# MiniWitch-Hardware.net
KiCad netlist of a schematic drawn in EasyEDA Pro
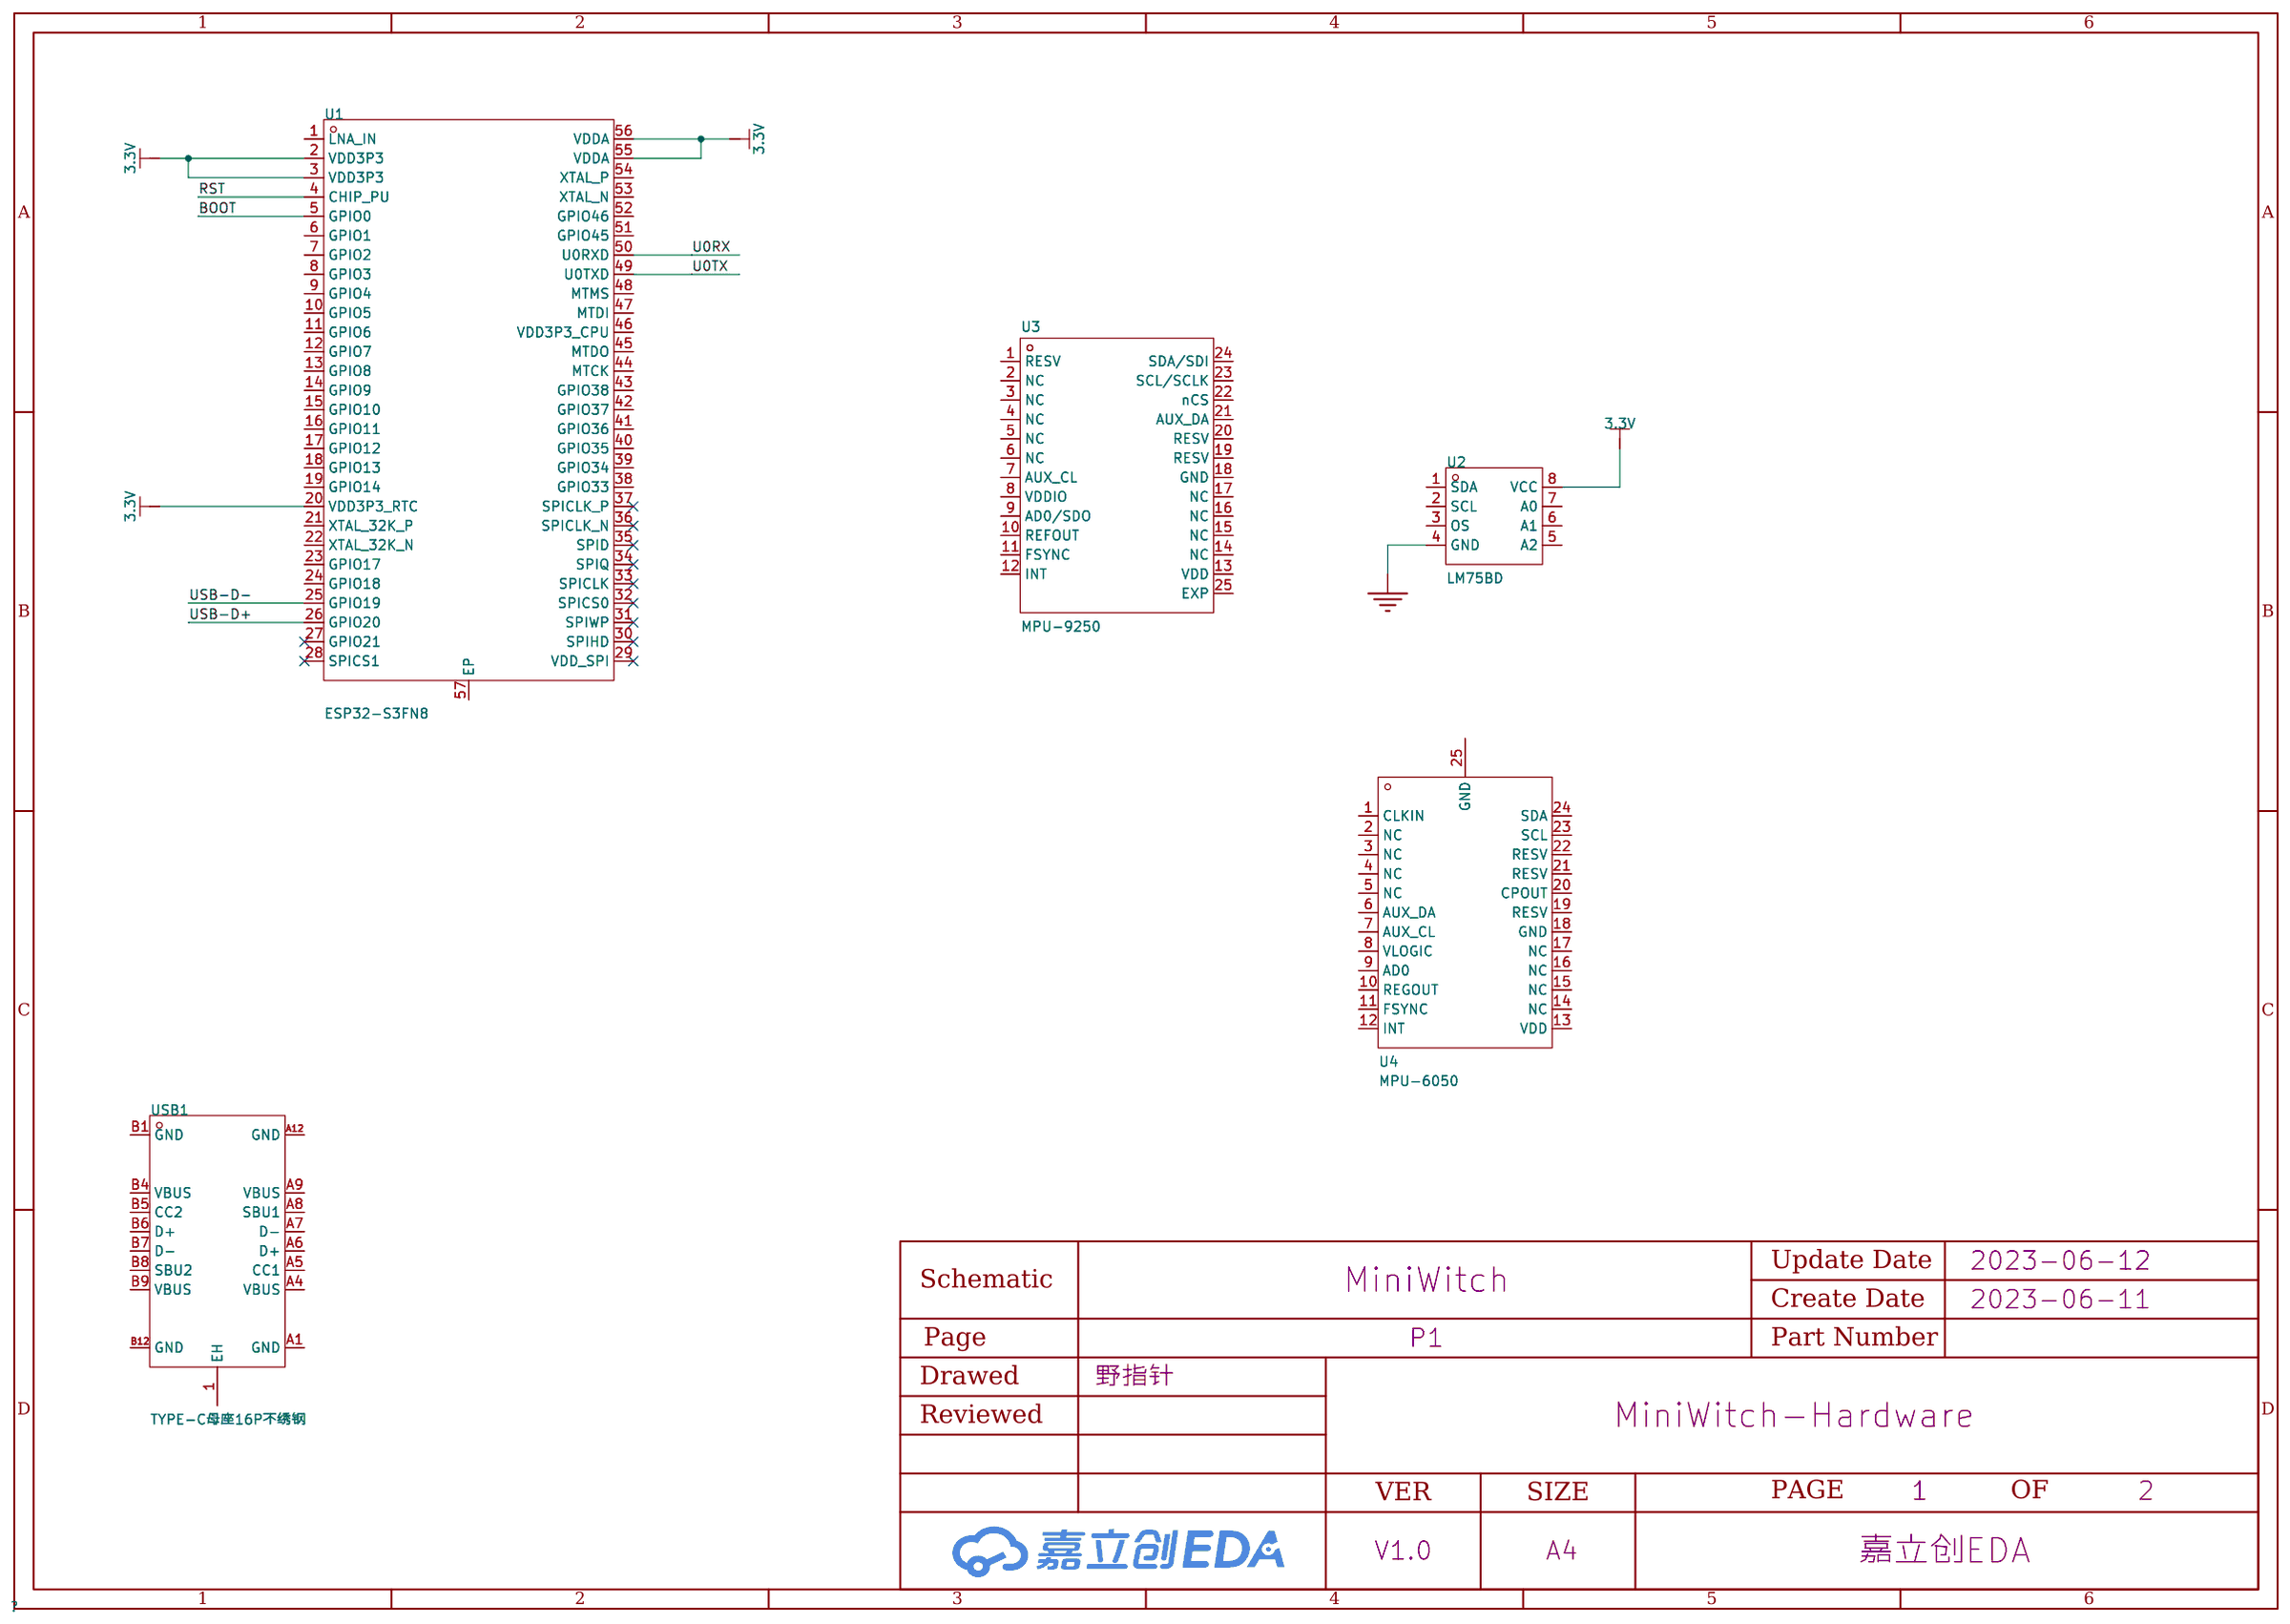
[diagram p0: P1]
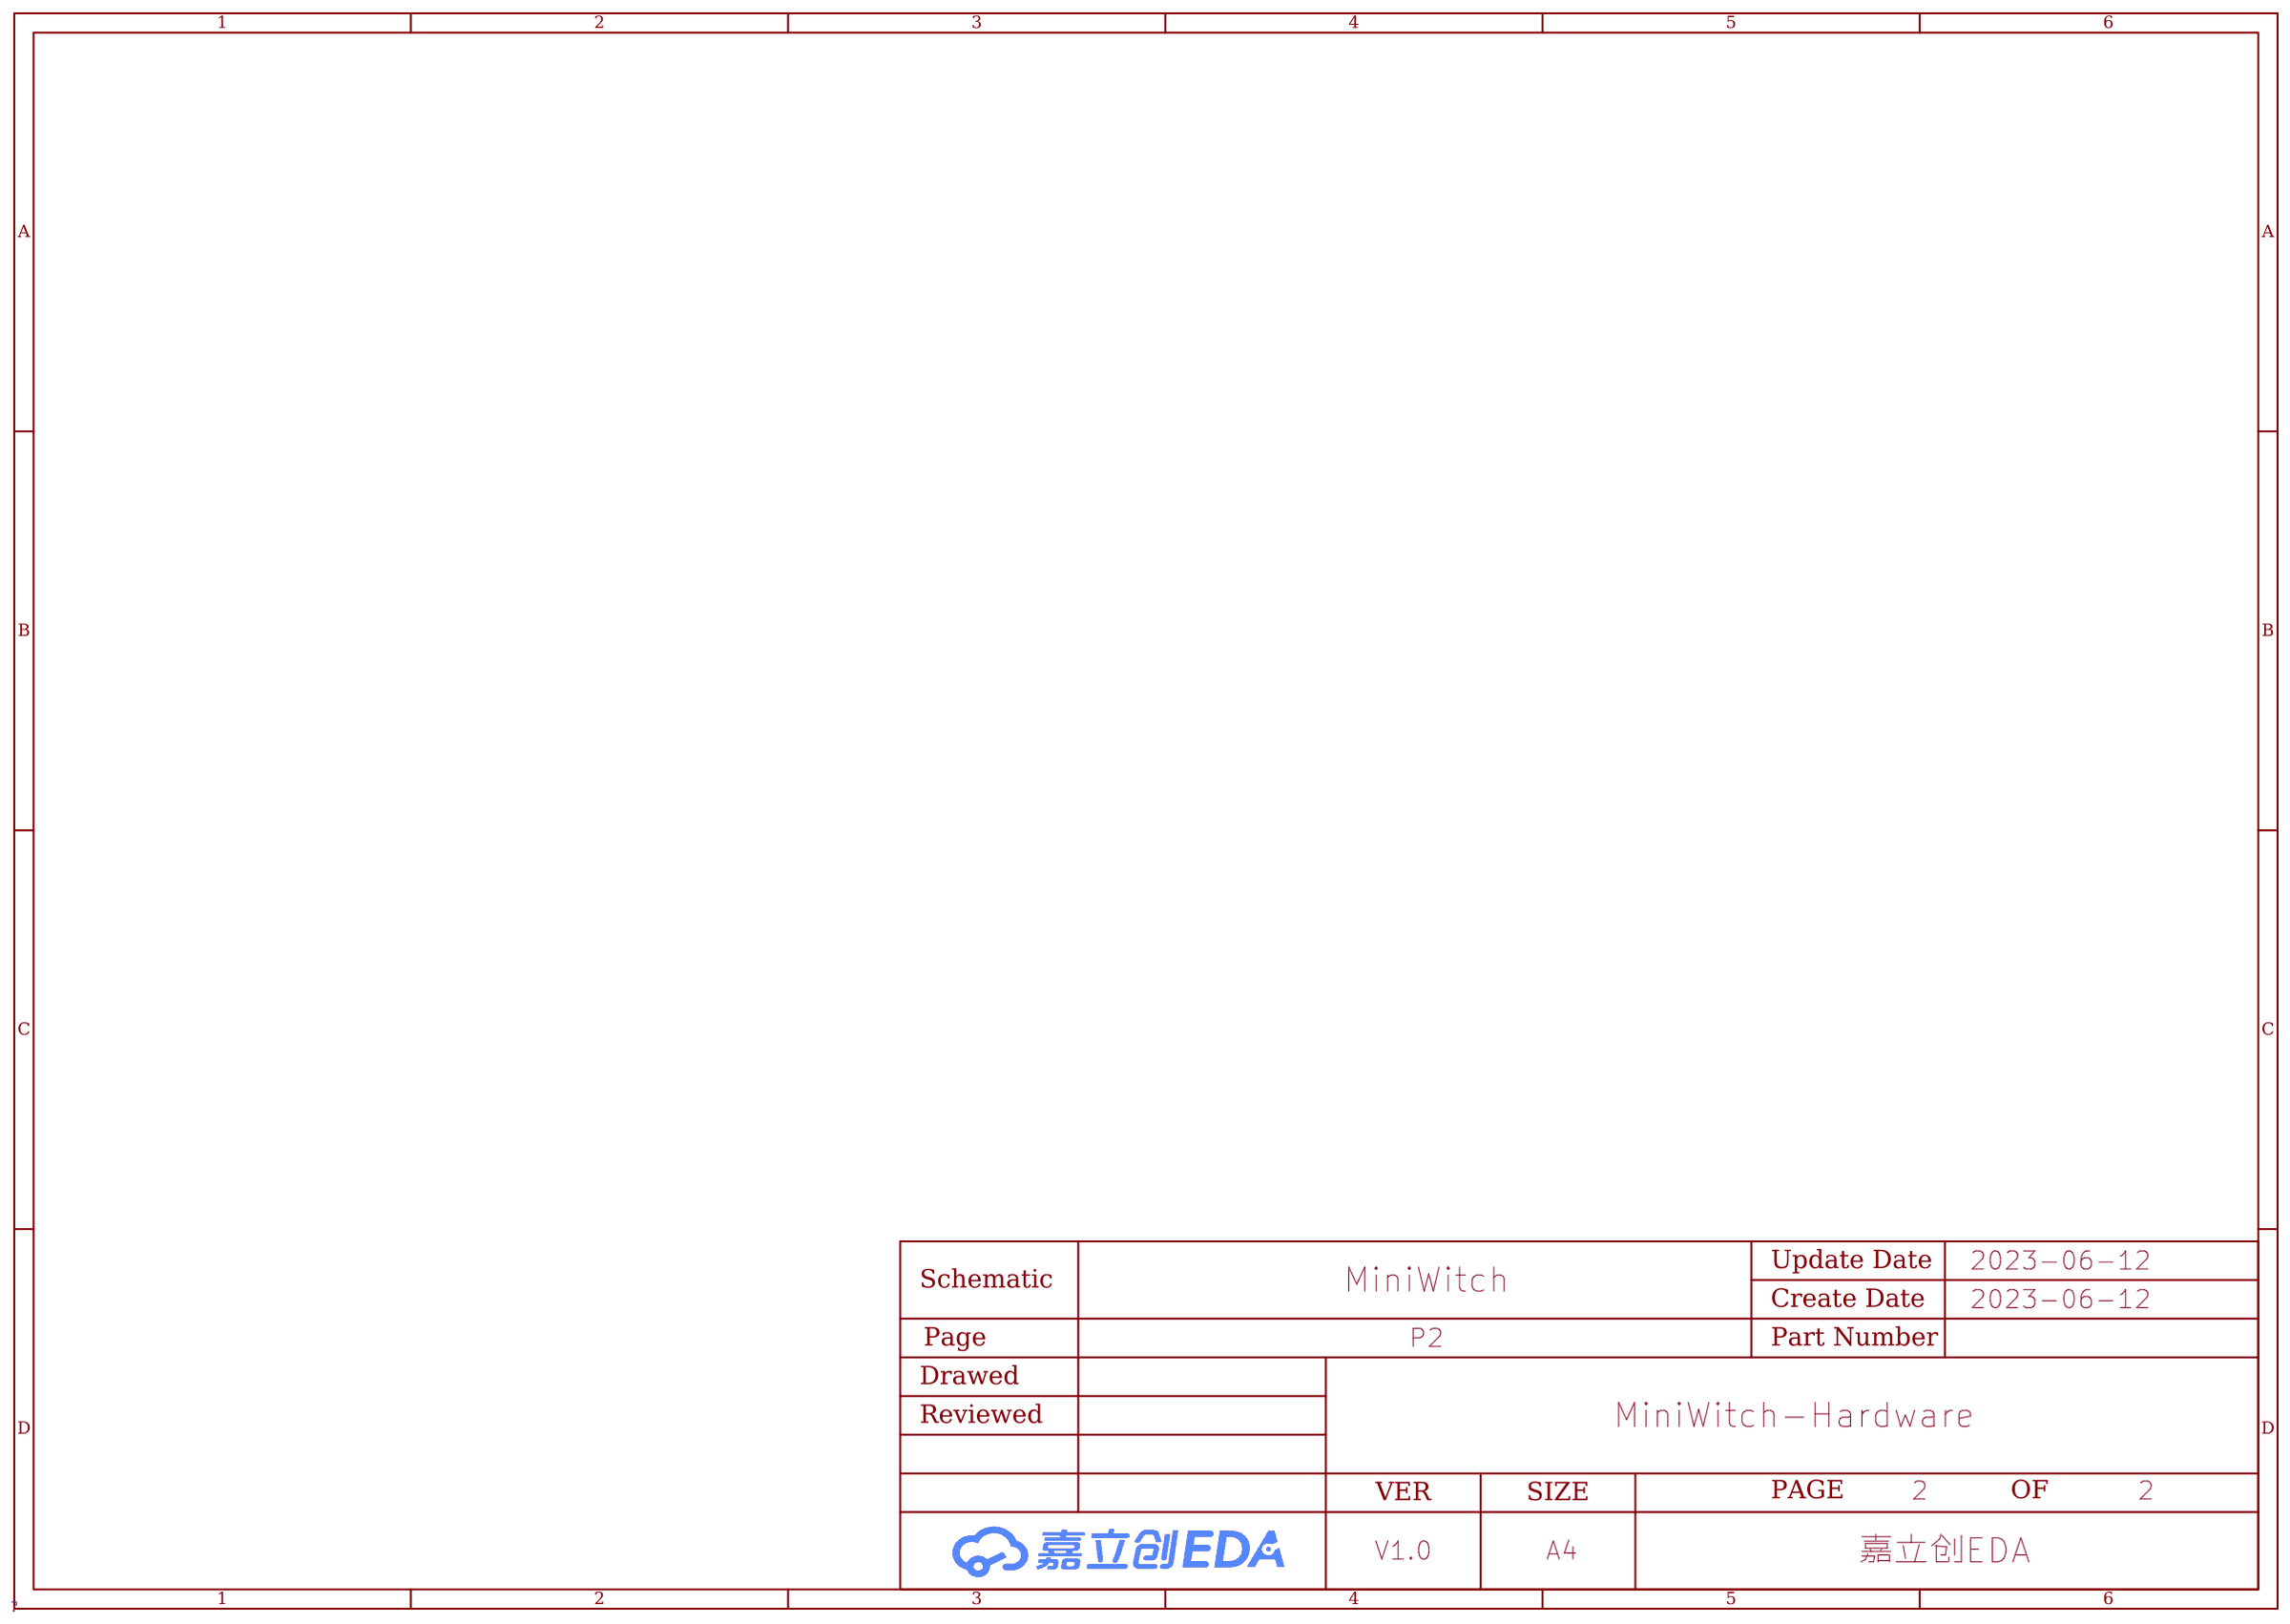
[diagram p1: P2]

(export (version "E")
  (design (tool "Eeschema 10.0.6"))
  (components
    (comp (ref "U1")
      (value "ESP32-S3FN8")
      (footprint "easyedapro:QFN-56_L7.0-W7.0-P0.40-TL-EP4.0")
      (fields (field (name "Manufacturer") "ESPRESSIF(乐鑫)"))
      (libsource (lib "easyedapro") (part "ESP32-S3"))
    )
    (comp (ref "U2")
      (value "LM75BD")
      (footprint "easyedapro:SOIC-8_L4.9-W3.9-P1.27-LS6.0-BL")
      (fields (field (name "Manufacturer") "UMW(友台半导体)"))
      (libsource (lib "easyedapro") (part "LM75BD"))
    )
    (comp (ref "U3")
      (value "MPU-9250")
      (footprint "easyedapro:QFN-24_L3.0-W3.0-P0.40-BL-EP")
      (description "9轴传感器")
      (fields (field (name "Manufacturer") "TDK InvenSense(应美盛)"))
      (libsource (lib "easyedapro") (part "MPU-9250"))
    )
    (comp (ref "U4")
      (value "MPU-6050")
      (footprint "easyedapro:QFN-24_L4.0-W4.0-P0.50-BL-EP2.7")
      (description "三轴加速度计和三轴陀螺仪，工作电压：2.375V~3.46V")
      (fields (field (name "Manufacturer") "TDK InvenSense(应美盛)"))
      (libsource (lib "easyedapro") (part "MPU-6050_C24112"))
    )
    (comp (ref "USB1")
      (value "TYPE-C母座16P不绣钢")
      (footprint "easyedapro:TYPE-C-SMD_16P-EH4")
      (libsource (lib "easyedapro") (part "TYPE-C母座16P不绣钢"))
    )
  )
  (nets
    (net (code "1") (name "3.3V") (class "Default")
      (node (ref "U1") (pin "2") (pinfunction "VDD3P3_2") (pintype "input"))
      (node (ref "U1") (pin "20") (pinfunction "VDD3P3_RTC_20") (pintype "input"))
      (node (ref "U1") (pin "3") (pinfunction "VDD3P3_3") (pintype "input"))
      (node (ref "U1") (pin "55") (pinfunction "VDDA_55") (pintype "input"))
      (node (ref "U1") (pin "56") (pinfunction "VDDA_56") (pintype "input"))
      (node (ref "U2") (pin "8") (pinfunction "VCC_8") (pintype "input"))
    )
    (net (code "2") (name "BOOT") (class "Default")
      (node (ref "U1") (pin "5") (pinfunction "GPIO0_5") (pintype "input"))
    )
    (net (code "3") (name "GND") (class "Default")
      (node (ref "U2") (pin "4") (pinfunction "GND_4") (pintype "input"))
    )
    (net (code "4") (name "RST") (class "Default")
      (node (ref "U1") (pin "4") (pinfunction "CHIP_PU_4") (pintype "input"))
    )
    (net (code "5") (name "U0RX") (class "Default")
      (node (ref "U1") (pin "50") (pinfunction "U0RXD_50") (pintype "input"))
    )
    (net (code "6") (name "U0TX") (class "Default")
      (node (ref "U1") (pin "49") (pinfunction "U0TXD_49") (pintype "input"))
    )
    (net (code "7") (name "USB-D+") (class "Default")
      (node (ref "U1") (pin "26") (pinfunction "GPIO20_26") (pintype "input"))
    )
    (net (code "8") (name "USB-D-") (class "Default")
      (node (ref "U1") (pin "25") (pinfunction "GPIO19_25") (pintype "input"))
    )
    (net (code "9") (name "unconnected-(U1-EP-Pad57)") (class "Default")
      (node (ref "U1") (pin "57") (pinfunction "EP_57") (pintype "input"))
    )
    (net (code "10") (name "unconnected-(U1-GPIO1-Pad6)") (class "Default")
      (node (ref "U1") (pin "6") (pinfunction "GPIO1_6") (pintype "input"))
    )
    (net (code "11") (name "unconnected-(U1-GPIO2-Pad7)") (class "Default")
      (node (ref "U1") (pin "7") (pinfunction "GPIO2_7") (pintype "input"))
    )
    (net (code "12") (name "unconnected-(U1-GPIO3-Pad8)") (class "Default")
      (node (ref "U1") (pin "8") (pinfunction "GPIO3_8") (pintype "input"))
    )
    (net (code "13") (name "unconnected-(U1-GPIO4-Pad9)") (class "Default")
      (node (ref "U1") (pin "9") (pinfunction "GPIO4_9") (pintype "input"))
    )
    (net (code "14") (name "unconnected-(U1-GPIO5-Pad10)") (class "Default")
      (node (ref "U1") (pin "10") (pinfunction "GPIO5_10") (pintype "input"))
    )
    (net (code "15") (name "unconnected-(U1-GPIO6-Pad11)") (class "Default")
      (node (ref "U1") (pin "11") (pinfunction "GPIO6_11") (pintype "input"))
    )
    (net (code "16") (name "unconnected-(U1-GPIO7-Pad12)") (class "Default")
      (node (ref "U1") (pin "12") (pinfunction "GPIO7_12") (pintype "input"))
    )
    (net (code "17") (name "unconnected-(U1-GPIO8-Pad13)") (class "Default")
      (node (ref "U1") (pin "13") (pinfunction "GPIO8_13") (pintype "input"))
    )
    (net (code "18") (name "unconnected-(U1-GPIO9-Pad14)") (class "Default")
      (node (ref "U1") (pin "14") (pinfunction "GPIO9_14") (pintype "input"))
    )
    (net (code "19") (name "unconnected-(U1-GPIO10-Pad15)") (class "Default")
      (node (ref "U1") (pin "15") (pinfunction "GPIO10_15") (pintype "input"))
    )
    (net (code "20") (name "unconnected-(U1-GPIO11-Pad16)") (class "Default")
      (node (ref "U1") (pin "16") (pinfunction "GPIO11_16") (pintype "input"))
    )
    (net (code "21") (name "unconnected-(U1-GPIO12-Pad17)") (class "Default")
      (node (ref "U1") (pin "17") (pinfunction "GPIO12_17") (pintype "input"))
    )
    (net (code "22") (name "unconnected-(U1-GPIO13-Pad18)") (class "Default")
      (node (ref "U1") (pin "18") (pinfunction "GPIO13_18") (pintype "input"))
    )
    (net (code "23") (name "unconnected-(U1-GPIO14-Pad19)") (class "Default")
      (node (ref "U1") (pin "19") (pinfunction "GPIO14_19") (pintype "input"))
    )
    (net (code "24") (name "unconnected-(U1-GPIO17-Pad23)") (class "Default")
      (node (ref "U1") (pin "23") (pinfunction "GPIO17_23") (pintype "input"))
    )
    (net (code "25") (name "unconnected-(U1-GPIO18-Pad24)") (class "Default")
      (node (ref "U1") (pin "24") (pinfunction "GPIO18_24") (pintype "input"))
    )
    (net (code "26") (name "unconnected-(U1-GPIO21-Pad27)") (class "Default")
      (node (ref "U1") (pin "27") (pinfunction "GPIO21_27") (pintype "input+no_connect"))
    )
    (net (code "27") (name "unconnected-(U1-GPIO33-Pad38)") (class "Default")
      (node (ref "U1") (pin "38") (pinfunction "GPIO33_38") (pintype "input"))
    )
    (net (code "28") (name "unconnected-(U1-GPIO34-Pad39)") (class "Default")
      (node (ref "U1") (pin "39") (pinfunction "GPIO34_39") (pintype "input"))
    )
    (net (code "29") (name "unconnected-(U1-GPIO35-Pad40)") (class "Default")
      (node (ref "U1") (pin "40") (pinfunction "GPIO35_40") (pintype "input"))
    )
    (net (code "30") (name "unconnected-(U1-GPIO36-Pad41)") (class "Default")
      (node (ref "U1") (pin "41") (pinfunction "GPIO36_41") (pintype "input"))
    )
    (net (code "31") (name "unconnected-(U1-GPIO37-Pad42)") (class "Default")
      (node (ref "U1") (pin "42") (pinfunction "GPIO37_42") (pintype "input"))
    )
    (net (code "32") (name "unconnected-(U1-GPIO38-Pad43)") (class "Default")
      (node (ref "U1") (pin "43") (pinfunction "GPIO38_43") (pintype "input"))
    )
    (net (code "33") (name "unconnected-(U1-GPIO45-Pad51)") (class "Default")
      (node (ref "U1") (pin "51") (pinfunction "GPIO45_51") (pintype "input"))
    )
    (net (code "34") (name "unconnected-(U1-GPIO46-Pad52)") (class "Default")
      (node (ref "U1") (pin "52") (pinfunction "GPIO46_52") (pintype "input"))
    )
    (net (code "35") (name "unconnected-(U1-LNA_IN-Pad1)") (class "Default")
      (node (ref "U1") (pin "1") (pinfunction "LNA_IN_1") (pintype "input"))
    )
    (net (code "36") (name "unconnected-(U1-MTCK-Pad44)") (class "Default")
      (node (ref "U1") (pin "44") (pinfunction "MTCK_44") (pintype "input"))
    )
    (net (code "37") (name "unconnected-(U1-MTDI-Pad47)") (class "Default")
      (node (ref "U1") (pin "47") (pinfunction "MTDI_47") (pintype "input"))
    )
    (net (code "38") (name "unconnected-(U1-MTDO-Pad45)") (class "Default")
      (node (ref "U1") (pin "45") (pinfunction "MTDO_45") (pintype "input"))
    )
    (net (code "39") (name "unconnected-(U1-MTMS-Pad48)") (class "Default")
      (node (ref "U1") (pin "48") (pinfunction "MTMS_48") (pintype "input"))
    )
    (net (code "40") (name "unconnected-(U1-SPICLK-Pad33)") (class "Default")
      (node (ref "U1") (pin "33") (pinfunction "SPICLK_33") (pintype "input+no_connect"))
    )
    (net (code "41") (name "unconnected-(U1-SPICLK_N-Pad36)") (class "Default")
      (node (ref "U1") (pin "36") (pinfunction "SPICLK_N_36") (pintype "input+no_connect"))
    )
    (net (code "42") (name "unconnected-(U1-SPICLK_P-Pad37)") (class "Default")
      (node (ref "U1") (pin "37") (pinfunction "SPICLK_P_37") (pintype "input+no_connect"))
    )
    (net (code "43") (name "unconnected-(U1-SPICS0-Pad32)") (class "Default")
      (node (ref "U1") (pin "32") (pinfunction "SPICS0_32") (pintype "input+no_connect"))
    )
    (net (code "44") (name "unconnected-(U1-SPICS1-Pad28)") (class "Default")
      (node (ref "U1") (pin "28") (pinfunction "SPICS1_28") (pintype "input+no_connect"))
    )
    (net (code "45") (name "unconnected-(U1-SPID-Pad35)") (class "Default")
      (node (ref "U1") (pin "35") (pinfunction "SPID_35") (pintype "input+no_connect"))
    )
    (net (code "46") (name "unconnected-(U1-SPIHD-Pad30)") (class "Default")
      (node (ref "U1") (pin "30") (pinfunction "SPIHD_30") (pintype "input+no_connect"))
    )
    (net (code "47") (name "unconnected-(U1-SPIQ-Pad34)") (class "Default")
      (node (ref "U1") (pin "34") (pinfunction "SPIQ_34") (pintype "input+no_connect"))
    )
    (net (code "48") (name "unconnected-(U1-SPIWP-Pad31)") (class "Default")
      (node (ref "U1") (pin "31") (pinfunction "SPIWP_31") (pintype "input+no_connect"))
    )
    (net (code "49") (name "unconnected-(U1-VDD3P3_CPU-Pad46)") (class "Default")
      (node (ref "U1") (pin "46") (pinfunction "VDD3P3_CPU_46") (pintype "input"))
    )
    (net (code "50") (name "unconnected-(U1-VDD_SPI-Pad29)") (class "Default")
      (node (ref "U1") (pin "29") (pinfunction "VDD_SPI_29") (pintype "input+no_connect"))
    )
    (net (code "51") (name "unconnected-(U1-XTAL_32K_N-Pad22)") (class "Default")
      (node (ref "U1") (pin "22") (pinfunction "XTAL_32K_N_22") (pintype "input"))
    )
    (net (code "52") (name "unconnected-(U1-XTAL_32K_P-Pad21)") (class "Default")
      (node (ref "U1") (pin "21") (pinfunction "XTAL_32K_P_21") (pintype "input"))
    )
    (net (code "53") (name "unconnected-(U1-XTAL_N-Pad53)") (class "Default")
      (node (ref "U1") (pin "53") (pinfunction "XTAL_N_53") (pintype "input"))
    )
    (net (code "54") (name "unconnected-(U1-XTAL_P-Pad54)") (class "Default")
      (node (ref "U1") (pin "54") (pinfunction "XTAL_P_54") (pintype "input"))
    )
    (net (code "55") (name "unconnected-(U2-A0-Pad7)") (class "Default")
      (node (ref "U2") (pin "7") (pinfunction "A0_7") (pintype "input"))
    )
    (net (code "56") (name "unconnected-(U2-A1-Pad6)") (class "Default")
      (node (ref "U2") (pin "6") (pinfunction "A1_6") (pintype "input"))
    )
    (net (code "57") (name "unconnected-(U2-A2-Pad5)") (class "Default")
      (node (ref "U2") (pin "5") (pinfunction "A2_5") (pintype "input"))
    )
    (net (code "58") (name "unconnected-(U2-OS-Pad3)") (class "Default")
      (node (ref "U2") (pin "3") (pinfunction "OS_3") (pintype "input"))
    )
    (net (code "59") (name "unconnected-(U2-SCL-Pad2)") (class "Default")
      (node (ref "U2") (pin "2") (pinfunction "SCL_2") (pintype "input"))
    )
    (net (code "60") (name "unconnected-(U2-SDA-Pad1)") (class "Default")
      (node (ref "U2") (pin "1") (pinfunction "SDA_1") (pintype "input"))
    )
    (net (code "61") (name "unconnected-(U3-AD0{slash}SDO-Pad9)") (class "Default")
      (node (ref "U3") (pin "9") (pinfunction "AD0/SDO_9") (pintype "input"))
    )
    (net (code "62") (name "unconnected-(U3-AUX_CL-Pad7)") (class "Default")
      (node (ref "U3") (pin "7") (pinfunction "AUX_CL_7") (pintype "input"))
    )
    (net (code "63") (name "unconnected-(U3-AUX_DA-Pad21)") (class "Default")
      (node (ref "U3") (pin "21") (pinfunction "AUX_DA_21") (pintype "input"))
    )
    (net (code "64") (name "unconnected-(U3-EXP-Pad25)") (class "Default")
      (node (ref "U3") (pin "25") (pinfunction "EXP_25") (pintype "input"))
    )
    (net (code "65") (name "unconnected-(U3-FSYNC-Pad11)") (class "Default")
      (node (ref "U3") (pin "11") (pinfunction "FSYNC_11") (pintype "input"))
    )
    (net (code "66") (name "unconnected-(U3-GND-Pad18)") (class "Default")
      (node (ref "U3") (pin "18") (pinfunction "GND_18") (pintype "input"))
    )
    (net (code "67") (name "unconnected-(U3-INT-Pad12)") (class "Default")
      (node (ref "U3") (pin "12") (pinfunction "INT_12") (pintype "input"))
    )
    (net (code "68") (name "unconnected-(U3-NC-Pad2)") (class "Default")
      (node (ref "U3") (pin "2") (pinfunction "NC_2") (pintype "input"))
    )
    (net (code "69") (name "unconnected-(U3-NC-Pad3)") (class "Default")
      (node (ref "U3") (pin "3") (pinfunction "NC_3") (pintype "input"))
    )
    (net (code "70") (name "unconnected-(U3-NC-Pad4)") (class "Default")
      (node (ref "U3") (pin "4") (pinfunction "NC_4") (pintype "input"))
    )
    (net (code "71") (name "unconnected-(U3-NC-Pad5)") (class "Default")
      (node (ref "U3") (pin "5") (pinfunction "NC_5") (pintype "input"))
    )
    (net (code "72") (name "unconnected-(U3-NC-Pad6)") (class "Default")
      (node (ref "U3") (pin "6") (pinfunction "NC_6") (pintype "input"))
    )
    (net (code "73") (name "unconnected-(U3-NC-Pad14)") (class "Default")
      (node (ref "U3") (pin "14") (pinfunction "NC_14") (pintype "input"))
    )
    (net (code "74") (name "unconnected-(U3-NC-Pad15)") (class "Default")
      (node (ref "U3") (pin "15") (pinfunction "NC_15") (pintype "input"))
    )
    (net (code "75") (name "unconnected-(U3-NC-Pad16)") (class "Default")
      (node (ref "U3") (pin "16") (pinfunction "NC_16") (pintype "input"))
    )
    (net (code "76") (name "unconnected-(U3-NC-Pad17)") (class "Default")
      (node (ref "U3") (pin "17") (pinfunction "NC_17") (pintype "input"))
    )
    (net (code "77") (name "unconnected-(U3-REFOUT-Pad10)") (class "Default")
      (node (ref "U3") (pin "10") (pinfunction "REFOUT_10") (pintype "input"))
    )
    (net (code "78") (name "unconnected-(U3-RESV-Pad1)") (class "Default")
      (node (ref "U3") (pin "1") (pinfunction "RESV_1") (pintype "input"))
    )
    (net (code "79") (name "unconnected-(U3-RESV-Pad19)") (class "Default")
      (node (ref "U3") (pin "19") (pinfunction "RESV_19") (pintype "input"))
    )
    (net (code "80") (name "unconnected-(U3-RESV-Pad20)") (class "Default")
      (node (ref "U3") (pin "20") (pinfunction "RESV_20") (pintype "input"))
    )
    (net (code "81") (name "unconnected-(U3-SCL{slash}SCLK-Pad23)") (class "Default")
      (node (ref "U3") (pin "23") (pinfunction "SCL/SCLK_23") (pintype "input"))
    )
    (net (code "82") (name "unconnected-(U3-SDA{slash}SDI-Pad24)") (class "Default")
      (node (ref "U3") (pin "24") (pinfunction "SDA/SDI_24") (pintype "input"))
    )
    (net (code "83") (name "unconnected-(U3-VDD-Pad13)") (class "Default")
      (node (ref "U3") (pin "13") (pinfunction "VDD_13") (pintype "input"))
    )
    (net (code "84") (name "unconnected-(U3-VDDIO-Pad8)") (class "Default")
      (node (ref "U3") (pin "8") (pinfunction "VDDIO_8") (pintype "input"))
    )
    (net (code "85") (name "unconnected-(U3-nCS-Pad22)") (class "Default")
      (node (ref "U3") (pin "22") (pinfunction "nCS_22") (pintype "input"))
    )
    (net (code "86") (name "unconnected-(U4-AD0-Pad9)") (class "Default")
      (node (ref "U4") (pin "9") (pinfunction "AD0_9") (pintype "input"))
    )
    (net (code "87") (name "unconnected-(U4-AUX_CL-Pad7)") (class "Default")
      (node (ref "U4") (pin "7") (pinfunction "AUX_CL_7") (pintype "input"))
    )
    (net (code "88") (name "unconnected-(U4-AUX_DA-Pad6)") (class "Default")
      (node (ref "U4") (pin "6") (pinfunction "AUX_DA_6") (pintype "input"))
    )
    (net (code "89") (name "unconnected-(U4-CLKIN-Pad1)") (class "Default")
      (node (ref "U4") (pin "1") (pinfunction "CLKIN_1") (pintype "input"))
    )
    (net (code "90") (name "unconnected-(U4-CPOUT-Pad20)") (class "Default")
      (node (ref "U4") (pin "20") (pinfunction "CPOUT_20") (pintype "input"))
    )
    (net (code "91") (name "unconnected-(U4-FSYNC-Pad11)") (class "Default")
      (node (ref "U4") (pin "11") (pinfunction "FSYNC_11") (pintype "input"))
    )
    (net (code "92") (name "unconnected-(U4-GND-Pad18)") (class "Default")
      (node (ref "U4") (pin "18") (pinfunction "GND_18") (pintype "input"))
    )
    (net (code "93") (name "unconnected-(U4-GND-Pad25)") (class "Default")
      (node (ref "U4") (pin "25") (pinfunction "GND_25") (pintype "input"))
    )
    (net (code "94") (name "unconnected-(U4-INT-Pad12)") (class "Default")
      (node (ref "U4") (pin "12") (pinfunction "INT_12") (pintype "input"))
    )
    (net (code "95") (name "unconnected-(U4-NC-Pad2)") (class "Default")
      (node (ref "U4") (pin "2") (pinfunction "NC_2") (pintype "input"))
    )
    (net (code "96") (name "unconnected-(U4-NC-Pad3)") (class "Default")
      (node (ref "U4") (pin "3") (pinfunction "NC_3") (pintype "input"))
    )
    (net (code "97") (name "unconnected-(U4-NC-Pad4)") (class "Default")
      (node (ref "U4") (pin "4") (pinfunction "NC_4") (pintype "input"))
    )
    (net (code "98") (name "unconnected-(U4-NC-Pad5)") (class "Default")
      (node (ref "U4") (pin "5") (pinfunction "NC_5") (pintype "input"))
    )
    (net (code "99") (name "unconnected-(U4-NC-Pad14)") (class "Default")
      (node (ref "U4") (pin "14") (pinfunction "NC_14") (pintype "input"))
    )
    (net (code "100") (name "unconnected-(U4-NC-Pad15)") (class "Default")
      (node (ref "U4") (pin "15") (pinfunction "NC_15") (pintype "input"))
    )
    (net (code "101") (name "unconnected-(U4-NC-Pad16)") (class "Default")
      (node (ref "U4") (pin "16") (pinfunction "NC_16") (pintype "input"))
    )
    (net (code "102") (name "unconnected-(U4-NC-Pad17)") (class "Default")
      (node (ref "U4") (pin "17") (pinfunction "NC_17") (pintype "input"))
    )
    (net (code "103") (name "unconnected-(U4-REGOUT-Pad10)") (class "Default")
      (node (ref "U4") (pin "10") (pinfunction "REGOUT_10") (pintype "input"))
    )
    (net (code "104") (name "unconnected-(U4-RESV-Pad19)") (class "Default")
      (node (ref "U4") (pin "19") (pinfunction "RESV_19") (pintype "input"))
    )
    (net (code "105") (name "unconnected-(U4-RESV-Pad21)") (class "Default")
      (node (ref "U4") (pin "21") (pinfunction "RESV_21") (pintype "input"))
    )
    (net (code "106") (name "unconnected-(U4-RESV-Pad22)") (class "Default")
      (node (ref "U4") (pin "22") (pinfunction "RESV_22") (pintype "input"))
    )
    (net (code "107") (name "unconnected-(U4-SCL-Pad23)") (class "Default")
      (node (ref "U4") (pin "23") (pinfunction "SCL_23") (pintype "input"))
    )
    (net (code "108") (name "unconnected-(U4-SDA-Pad24)") (class "Default")
      (node (ref "U4") (pin "24") (pinfunction "SDA_24") (pintype "input"))
    )
    (net (code "109") (name "unconnected-(U4-VDD-Pad13)") (class "Default")
      (node (ref "U4") (pin "13") (pinfunction "VDD_13") (pintype "input"))
    )
    (net (code "110") (name "unconnected-(U4-VLOGIC-Pad8)") (class "Default")
      (node (ref "U4") (pin "8") (pinfunction "VLOGIC_8") (pintype "input"))
    )
    (net (code "111") (name "unconnected-(USB1-CC1-PadA5)") (class "Default")
      (node (ref "USB1") (pin "A5") (pinfunction "CC1_A5") (pintype "input"))
    )
    (net (code "112") (name "unconnected-(USB1-CC2-PadB5)") (class "Default")
      (node (ref "USB1") (pin "B5") (pinfunction "CC2_B5") (pintype "input"))
    )
    (net (code "113") (name "unconnected-(USB1-D+-PadA6)") (class "Default")
      (node (ref "USB1") (pin "A6") (pinfunction "D+_A6") (pintype "input"))
    )
    (net (code "114") (name "unconnected-(USB1-D+-PadB6)") (class "Default")
      (node (ref "USB1") (pin "B6") (pinfunction "D+_B6") (pintype "input"))
    )
    (net (code "115") (name "unconnected-(USB1-D--PadA7)") (class "Default")
      (node (ref "USB1") (pin "A7") (pinfunction "D-_A7") (pintype "input"))
    )
    (net (code "116") (name "unconnected-(USB1-D--PadB7)") (class "Default")
      (node (ref "USB1") (pin "B7") (pinfunction "D-_B7") (pintype "input"))
    )
    (net (code "117") (name "unconnected-(USB1-EH-Pad1)") (class "Default")
      (node (ref "USB1") (pin "1") (pinfunction "EH_1") (pintype "input"))
    )
    (net (code "118") (name "unconnected-(USB1-GND-PadA1)") (class "Default")
      (node (ref "USB1") (pin "A1") (pinfunction "GND_A1") (pintype "input"))
    )
    (net (code "119") (name "unconnected-(USB1-GND-PadA12)") (class "Default")
      (node (ref "USB1") (pin "A12") (pinfunction "GND_A12") (pintype "input"))
    )
    (net (code "120") (name "unconnected-(USB1-GND-PadB1)") (class "Default")
      (node (ref "USB1") (pin "B1") (pinfunction "GND_B1") (pintype "input"))
    )
    (net (code "121") (name "unconnected-(USB1-GND-PadB12)") (class "Default")
      (node (ref "USB1") (pin "B12") (pinfunction "GND_B12") (pintype "input"))
    )
    (net (code "122") (name "unconnected-(USB1-SBU1-PadA8)") (class "Default")
      (node (ref "USB1") (pin "A8") (pinfunction "SBU1_A8") (pintype "input"))
    )
    (net (code "123") (name "unconnected-(USB1-SBU2-PadB8)") (class "Default")
      (node (ref "USB1") (pin "B8") (pinfunction "SBU2_B8") (pintype "input"))
    )
    (net (code "124") (name "unconnected-(USB1-VBUS-PadA4)") (class "Default")
      (node (ref "USB1") (pin "A4") (pinfunction "VBUS_A4") (pintype "input"))
    )
    (net (code "125") (name "unconnected-(USB1-VBUS-PadA9)") (class "Default")
      (node (ref "USB1") (pin "A9") (pinfunction "VBUS_A9") (pintype "input"))
    )
    (net (code "126") (name "unconnected-(USB1-VBUS-PadB4)") (class "Default")
      (node (ref "USB1") (pin "B4") (pinfunction "VBUS_B4") (pintype "input"))
    )
    (net (code "127") (name "unconnected-(USB1-VBUS-PadB9)") (class "Default")
      (node (ref "USB1") (pin "B9") (pinfunction "VBUS_B9") (pintype "input"))
    )
  )
)
